# El_W_rfel.net
KiCad netlist of a schematic drawn in EAGLE
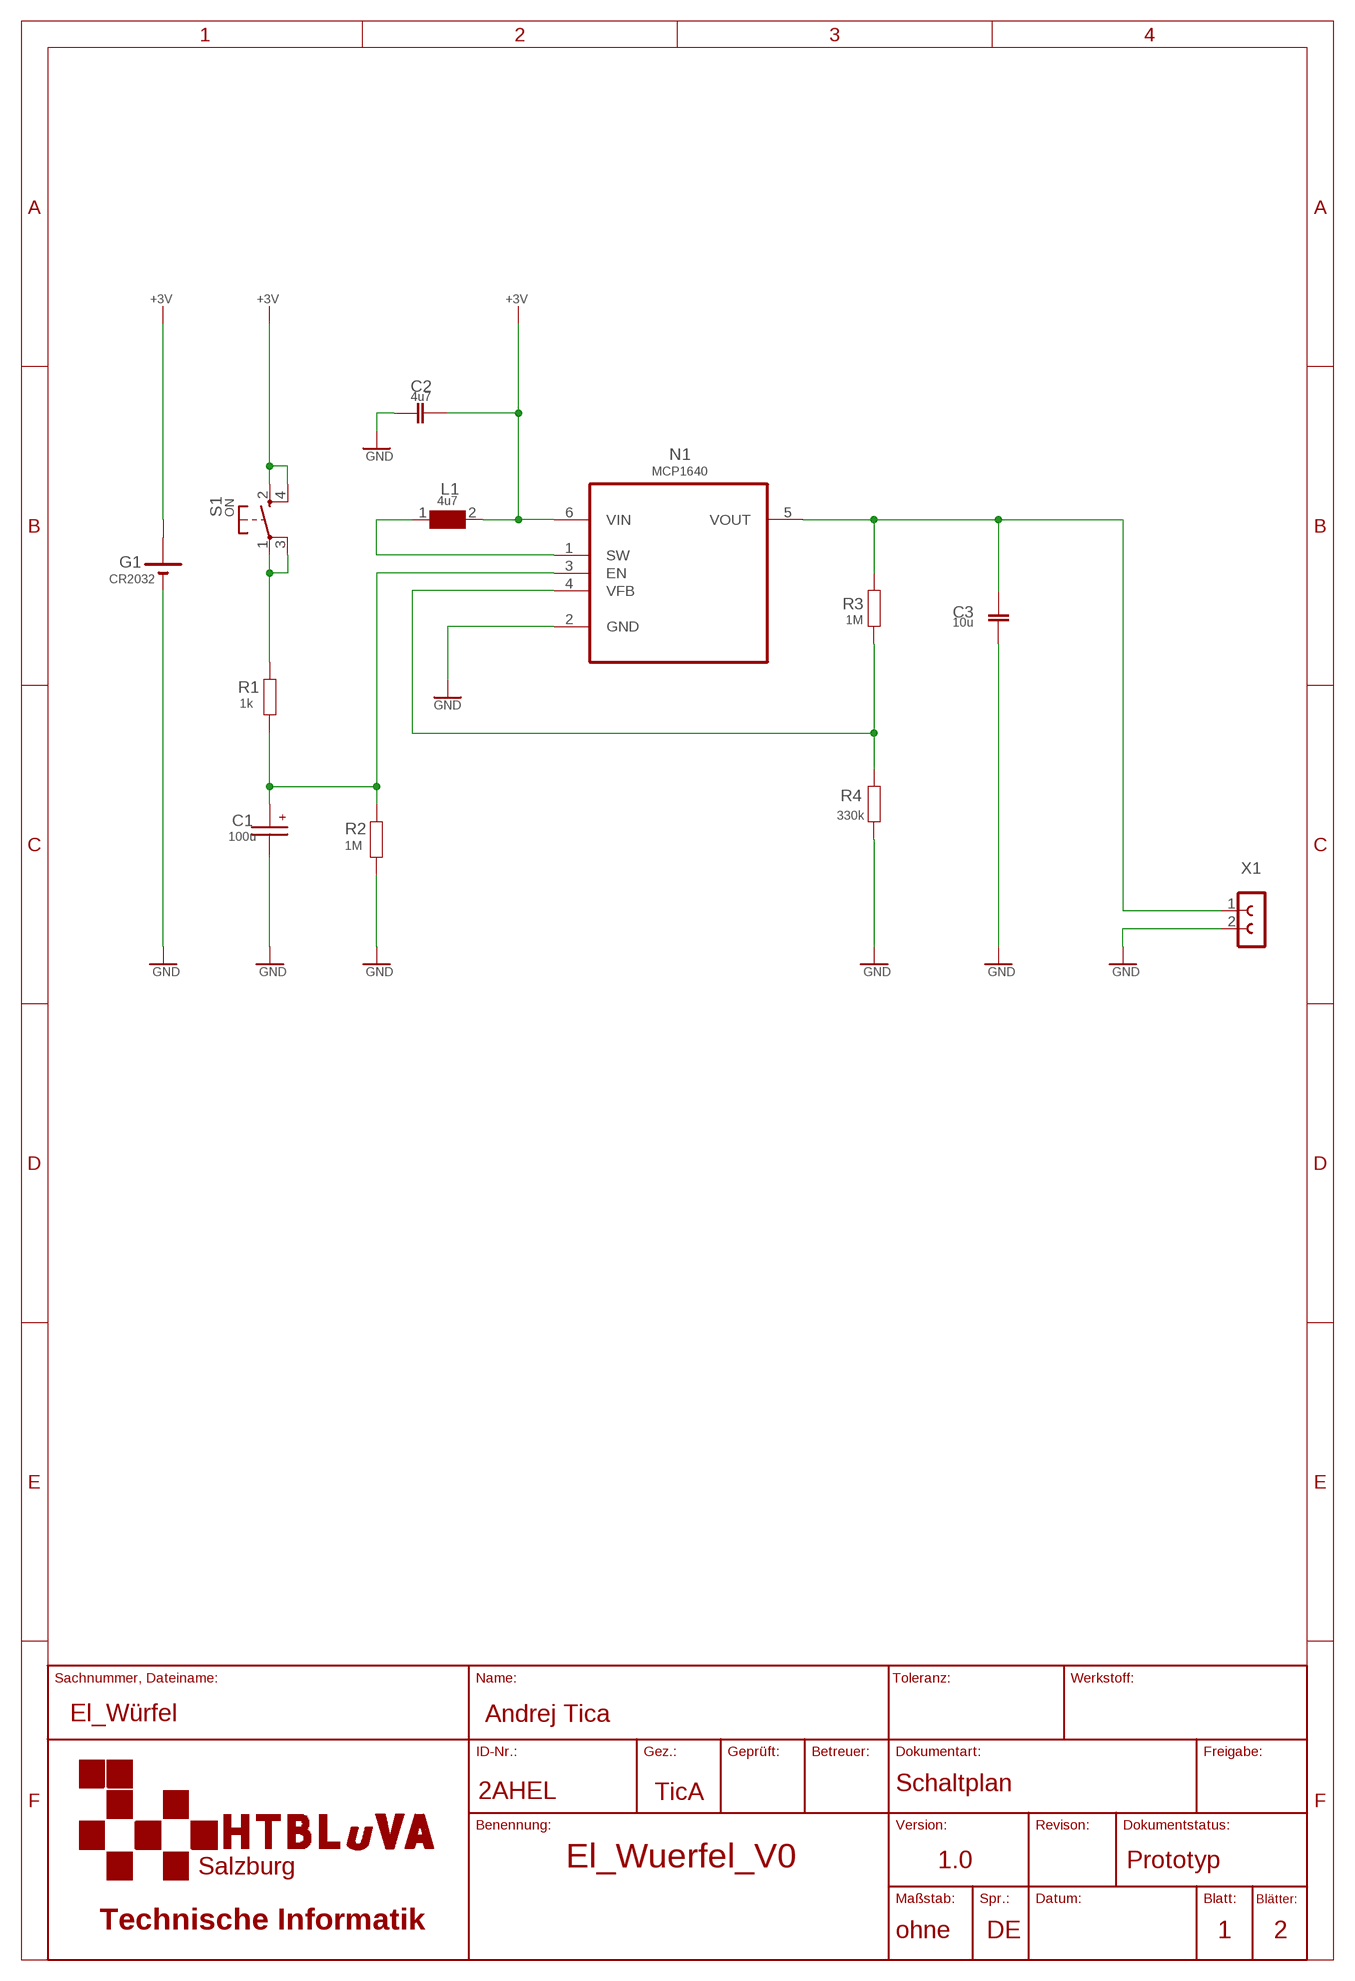
[diagram p0: schematic, sheet 1]
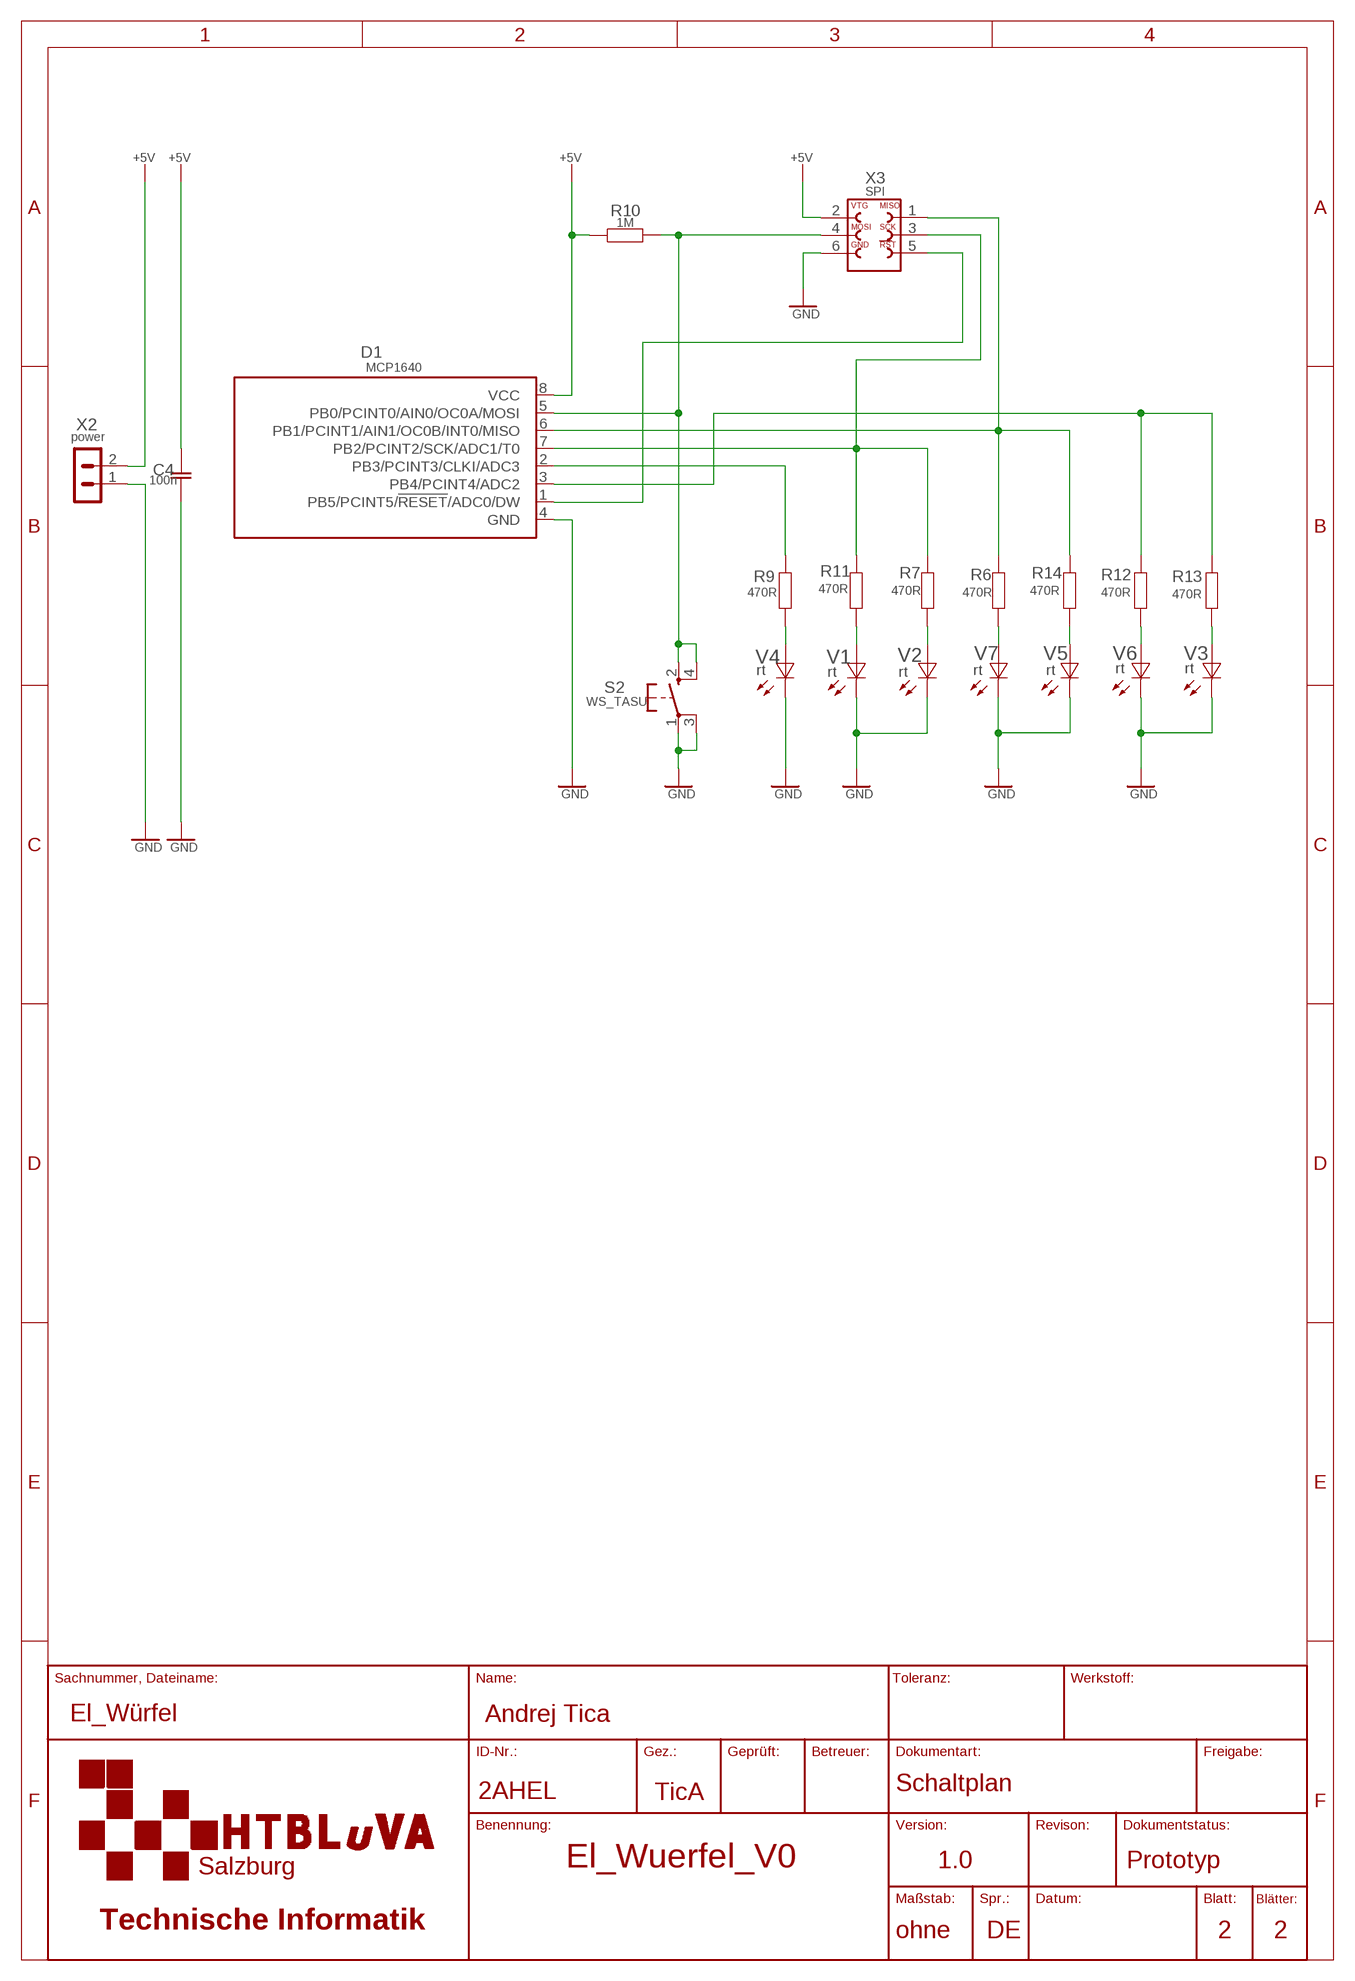
[diagram p1: schematic, sheet 2]

(export (version "E")
  (design (tool "Eeschema 10.0.6"))
  (components
    (comp (ref "C1")
      (value "100u")
      (footprint "eagle-import:B_3528-21R")
      (libsource (lib "eagle-import") (part "CPOL-V_B/3528-21R"))
    )
    (comp (ref "C2")
      (value "4u7")
      (footprint "eagle-import:MYLIB_C1206")
      (libsource (lib "eagle-import") (part "rcl_TicA_C-EU1206"))
    )
    (comp (ref "C3")
      (value "10u")
      (footprint "eagle-import:MYLIB_C1206")
      (libsource (lib "eagle-import") (part "rcl_TicA_C-EU1206"))
    )
    (comp (ref "G1")
      (value "CR2032")
      (footprint "eagle-import:MYLIB_CR2032")
      (libsource (lib "eagle-import") (part "KNOPFZELLE3V2CR"))
    )
    (comp (ref "L1")
      (value "4u7")
      (footprint "eagle-import:WE-PD2_4532")
      (libsource (lib "eagle-import") (part "WE-PD2_4532"))
    )
    (comp (ref "N1")
      (value "MCP1640")
      (footprint "eagle-import:SOT95P270X145-6N")
      (fields (field (name "MPN") "MCP1640BT-I/CHY"))
      (libsource (lib "eagle-import") (part "MCP1640BT-I/CHY"))
    )
    (comp (ref "R1")
      (value "1k")
      (footprint "eagle-import:MYRCL_R1206")
      (libsource (lib "eagle-import") (part "Netzteil_WenN2016_RCL_R-EU_R1206"))
    )
    (comp (ref "R2")
      (value "1M")
      (footprint "eagle-import:MYRCL_R1206")
      (libsource (lib "eagle-import") (part "Netzteil_WenN2016_RCL_R-EU_R1206"))
    )
    (comp (ref "R3")
      (value "1M")
      (footprint "eagle-import:MYRCL_R1206")
      (libsource (lib "eagle-import") (part "Netzteil_WenN2016_RCL_R-EU_R1206"))
    )
    (comp (ref "R4")
      (value "330k")
      (footprint "eagle-import:MYRCL_R1206")
      (libsource (lib "eagle-import") (part "Netzteil_WenN2016_RCL_R-EU_R1206"))
    )
    (comp (ref "S1")
      (value "ON")
      (footprint "eagle-import:WE_436331045822")
      (libsource (lib "eagle-import") (part "TASTE10-XXSMD_LW"))
    )
    (comp (ref "X1")
      (value "BU-LEISTE2")
      (footprint "eagle-import:1X02-SPF-WW")
      (libsource (lib "eagle-import") (part "BU-LEISTE2"))
    )
    (comp (ref "C4")
      (value "100n")
      (footprint "eagle-import:MYLIB_C1206")
      (libsource (lib "eagle-import") (part "C-EU1206"))
    )
    (comp (ref "D1")
      (value "MCP1640")
      (footprint "eagle-import:8S2_W")
      (libsource (lib "eagle-import") (part "TINY13SF"))
    )
    (comp (ref "R6")
      (value "470R")
      (footprint "eagle-import:MYRCL_M1206")
      (libsource (lib "eagle-import") (part "RCL_R-EU_M1206"))
    )
    (comp (ref "R7")
      (value "470R")
      (footprint "eagle-import:MYRCL_M1206")
      (libsource (lib "eagle-import") (part "RCL_R-EU_M1206"))
    )
    (comp (ref "R9")
      (value "470R")
      (footprint "eagle-import:MYRCL_M1206")
      (libsource (lib "eagle-import") (part "RCL_R-EU_M1206"))
    )
    (comp (ref "R10")
      (value "1M")
      (footprint "eagle-import:MYRCL_M1206")
      (libsource (lib "eagle-import") (part "RCL_R-EU_M1206"))
    )
    (comp (ref "R11")
      (value "470R")
      (footprint "eagle-import:MYRCL_M1206")
      (libsource (lib "eagle-import") (part "RCL_R-EU_M1206"))
    )
    (comp (ref "R12")
      (value "470R")
      (footprint "eagle-import:MYRCL_M1206")
      (libsource (lib "eagle-import") (part "RCL_R-EU_M1206"))
    )
    (comp (ref "R13")
      (value "470R")
      (footprint "eagle-import:MYRCL_M1206")
      (libsource (lib "eagle-import") (part "RCL_R-EU_M1206"))
    )
    (comp (ref "R14")
      (value "470R")
      (footprint "eagle-import:MYRCL_M1206")
      (libsource (lib "eagle-import") (part "RCL_R-EU_M1206"))
    )
    (comp (ref "S2")
      (value "WS_TASU")
      (footprint "eagle-import:WE_436331045822")
      (libsource (lib "eagle-import") (part "TASTE10-XXWE"))
    )
    (comp (ref "V1")
      (value "rt")
      (footprint "eagle-import:MYDIODE_CHIPLED_1206")
      (libsource (lib "eagle-import") (part "DIODE_LEDCHIPLED_1206"))
    )
    (comp (ref "V2")
      (value "rt")
      (footprint "eagle-import:MYDIODE_CHIPLED_1206")
      (libsource (lib "eagle-import") (part "DIODE_LEDCHIPLED_1206"))
    )
    (comp (ref "V3")
      (value "rt")
      (footprint "eagle-import:MYDIODE_CHIPLED_1206")
      (libsource (lib "eagle-import") (part "DIODE_LEDCHIPLED_1206"))
    )
    (comp (ref "V4")
      (value "rt")
      (footprint "eagle-import:MYDIODE_CHIPLED_1206")
      (libsource (lib "eagle-import") (part "DIODE_LEDCHIPLED_1206"))
    )
    (comp (ref "V5")
      (value "rt")
      (footprint "eagle-import:MYDIODE_CHIPLED_1206")
      (libsource (lib "eagle-import") (part "DIODE_LEDCHIPLED_1206"))
    )
    (comp (ref "V6")
      (value "rt")
      (footprint "eagle-import:MYDIODE_CHIPLED_1206")
      (libsource (lib "eagle-import") (part "DIODE_LEDCHIPLED_1206"))
    )
    (comp (ref "V7")
      (value "rt")
      (footprint "eagle-import:MYDIODE_CHIPLED_1206")
      (libsource (lib "eagle-import") (part "DIODE_LEDCHIPLED_1206"))
    )
    (comp (ref "X2")
      (value "power")
      (footprint "eagle-import:02P")
      (libsource (lib "eagle-import") (part "M02"))
    )
    (comp (ref "X3")
      (value "SPI")
      (footprint "eagle-import:690367280676_NEU")
      (libsource (lib "eagle-import") (part "610006243021SMT_WR_MM_NEU"))
    )
  )
  (nets
    (net (code "1") (name "+3V") (class "Default")
      (node (ref "C2") (pin "-") (pinfunction "1_-") (pintype "passive"))
      (node (ref "G1") (pin "+@1") (pinfunction "+_+@1") (pintype "passive"))
      (node (ref "L1") (pin "2") (pinfunction "2_2") (pintype "passive"))
      (node (ref "N1") (pin "6") (pinfunction "VIN_6") (pintype "input"))
      (node (ref "S1") (pin "2") (pinfunction "S_2") (pintype "passive"))
      (node (ref "S1") (pin "4") (pinfunction "S1_4") (pintype "passive"))
    )
    (net (code "2") (name "+5V") (class "Default")
      (node (ref "C4") (pin "-") (pinfunction "1_-") (pintype "passive"))
      (node (ref "D1") (pin "8") (pinfunction "VCC_8") (pintype "power_in"))
      (node (ref "R10") (pin "1") (pinfunction "1_1") (pintype "passive"))
      (node (ref "X2") (pin "2") (pinfunction "2_2") (pintype "passive"))
      (node (ref "X3") (pin "2") (pinfunction "2_2") (pintype "passive"))
    )
    (net (code "3") (name "GND") (class "Default")
      (node (ref "C1") (pin "-") (pinfunction "-_-") (pintype "passive"))
      (node (ref "C2") (pin "+") (pinfunction "2_+") (pintype "passive"))
      (node (ref "C3") (pin "+") (pinfunction "2_+") (pintype "passive"))
      (node (ref "C4") (pin "+") (pinfunction "2_+") (pintype "passive"))
      (node (ref "D1") (pin "4") (pinfunction "GND_4") (pintype "power_in"))
      (node (ref "G1") (pin "-") (pinfunction "-_-") (pintype "passive"))
      (node (ref "N1") (pin "2") (pinfunction "GND_2") (pintype "passive"))
      (node (ref "R2") (pin "1") (pinfunction "1_1") (pintype "passive"))
      (node (ref "R4") (pin "1") (pinfunction "1_1") (pintype "passive"))
      (node (ref "S2") (pin "1") (pinfunction "P_1") (pintype "passive"))
      (node (ref "S2") (pin "3") (pinfunction "P1_3") (pintype "passive"))
      (node (ref "V1") (pin "C") (pinfunction "C_C") (pintype "passive"))
      (node (ref "V2") (pin "C") (pinfunction "C_C") (pintype "passive"))
      (node (ref "V3") (pin "C") (pinfunction "C_C") (pintype "passive"))
      (node (ref "V4") (pin "C") (pinfunction "C_C") (pintype "passive"))
      (node (ref "V5") (pin "C") (pinfunction "C_C") (pintype "passive"))
      (node (ref "V6") (pin "C") (pinfunction "C_C") (pintype "passive"))
      (node (ref "V7") (pin "C") (pinfunction "C_C") (pintype "passive"))
      (node (ref "X1") (pin "2") (pinfunction "2_2") (pintype "passive"))
      (node (ref "X2") (pin "1") (pinfunction "1_1") (pintype "passive"))
      (node (ref "X3") (pin "6") (pinfunction "6_6") (pintype "passive"))
    )
    (net (code "4") (name "Net-(C3-1)") (class "Default")
      (node (ref "C3") (pin "-") (pinfunction "1_-") (pintype "passive"))
      (node (ref "N1") (pin "5") (pinfunction "VOUT_5") (pintype "output"))
      (node (ref "R3") (pin "2") (pinfunction "2_2") (pintype "passive"))
      (node (ref "X1") (pin "1") (pinfunction "1_1") (pintype "passive"))
    )
    (net (code "5") (name "Net-(D1-PB0{slash}PCINT0{slash}AIN0{slash}OC0A{slash}MOSI)") (class "Default")
      (node (ref "D1") (pin "5") (pinfunction "PB0/PCINT0/AIN0/OC0A/MOSI_5") (pintype "bidirectional"))
      (node (ref "R10") (pin "2") (pinfunction "2_2") (pintype "passive"))
      (node (ref "S2") (pin "2") (pinfunction "S_2") (pintype "passive"))
      (node (ref "S2") (pin "4") (pinfunction "S1_4") (pintype "passive"))
      (node (ref "X3") (pin "4") (pinfunction "4_4") (pintype "passive"))
    )
    (net (code "6") (name "Net-(D1-PB1{slash}PCINT1{slash}AIN1{slash}OC0B{slash}INT0{slash}MISO)") (class "Default")
      (node (ref "D1") (pin "6") (pinfunction "PB1/PCINT1/AIN1/OC0B/INT0/MISO_6") (pintype "bidirectional"))
      (node (ref "R14") (pin "2") (pinfunction "2_2") (pintype "passive"))
      (node (ref "R6") (pin "2") (pinfunction "2_2") (pintype "passive"))
      (node (ref "X3") (pin "1") (pinfunction "1_1") (pintype "passive"))
    )
    (net (code "7") (name "Net-(D1-PB2{slash}PCINT2{slash}SCK{slash}ADC1{slash}T0)") (class "Default")
      (node (ref "D1") (pin "7") (pinfunction "PB2/PCINT2/SCK/ADC1/T0_7") (pintype "bidirectional"))
      (node (ref "R11") (pin "2") (pinfunction "2_2") (pintype "passive"))
      (node (ref "R7") (pin "2") (pinfunction "2_2") (pintype "passive"))
      (node (ref "X3") (pin "3") (pinfunction "3_3") (pintype "passive"))
    )
    (net (code "8") (name "Net-(D1-PB3{slash}PCINT3{slash}CLKI{slash}ADC3)") (class "Default")
      (node (ref "D1") (pin "2") (pinfunction "PB3/PCINT3/CLKI/ADC3_2") (pintype "bidirectional"))
      (node (ref "R9") (pin "2") (pinfunction "2_2") (pintype "passive"))
    )
    (net (code "9") (name "Net-(D1-PB4{slash}PCINT4{slash}ADC2)") (class "Default")
      (node (ref "D1") (pin "3") (pinfunction "PB4/PCINT4/ADC2_3") (pintype "bidirectional"))
      (node (ref "R12") (pin "2") (pinfunction "2_2") (pintype "passive"))
      (node (ref "R13") (pin "2") (pinfunction "2_2") (pintype "passive"))
    )
    (net (code "10") (name "Net-(D1-PB5{slash}PCINT5{slash}~{RESET}{slash}ADC0{slash}DW)") (class "Default")
      (node (ref "D1") (pin "1") (pinfunction "PB5/PCINT5/~{RESET}/ADC0/DW_1") (pintype "bidirectional"))
      (node (ref "X3") (pin "5") (pinfunction "5_5") (pintype "passive"))
    )
    (net (code "11") (name "Net-(N1-EN)") (class "Default")
      (node (ref "C1") (pin "+") (pinfunction "+_+") (pintype "passive"))
      (node (ref "N1") (pin "3") (pinfunction "EN_3") (pintype "input"))
      (node (ref "R1") (pin "1") (pinfunction "1_1") (pintype "passive"))
      (node (ref "R2") (pin "2") (pinfunction "2_2") (pintype "passive"))
    )
    (net (code "12") (name "Net-(N1-SW)") (class "Default")
      (node (ref "L1") (pin "1") (pinfunction "1_1") (pintype "passive"))
      (node (ref "N1") (pin "1") (pinfunction "SW_1") (pintype "input"))
    )
    (net (code "13") (name "Net-(N1-VFB)") (class "Default")
      (node (ref "N1") (pin "4") (pinfunction "VFB_4") (pintype "input"))
      (node (ref "R3") (pin "1") (pinfunction "1_1") (pintype "passive"))
      (node (ref "R4") (pin "2") (pinfunction "2_2") (pintype "passive"))
    )
    (net (code "14") (name "Net-(R6-Pad1)") (class "Default")
      (node (ref "R6") (pin "1") (pinfunction "1_1") (pintype "passive"))
      (node (ref "V7") (pin "A") (pinfunction "A_A") (pintype "passive"))
    )
    (net (code "15") (name "Net-(R7-Pad1)") (class "Default")
      (node (ref "R7") (pin "1") (pinfunction "1_1") (pintype "passive"))
      (node (ref "V2") (pin "A") (pinfunction "A_A") (pintype "passive"))
    )
    (net (code "16") (name "Net-(R9-Pad1)") (class "Default")
      (node (ref "R9") (pin "1") (pinfunction "1_1") (pintype "passive"))
      (node (ref "V4") (pin "A") (pinfunction "A_A") (pintype "passive"))
    )
    (net (code "17") (name "Net-(R11-Pad1)") (class "Default")
      (node (ref "R11") (pin "1") (pinfunction "1_1") (pintype "passive"))
      (node (ref "V1") (pin "A") (pinfunction "A_A") (pintype "passive"))
    )
    (net (code "18") (name "Net-(R12-Pad1)") (class "Default")
      (node (ref "R12") (pin "1") (pinfunction "1_1") (pintype "passive"))
      (node (ref "V6") (pin "A") (pinfunction "A_A") (pintype "passive"))
    )
    (net (code "19") (name "Net-(R13-Pad1)") (class "Default")
      (node (ref "R13") (pin "1") (pinfunction "1_1") (pintype "passive"))
      (node (ref "V3") (pin "A") (pinfunction "A_A") (pintype "passive"))
    )
    (net (code "20") (name "Net-(R14-Pad1)") (class "Default")
      (node (ref "R14") (pin "1") (pinfunction "1_1") (pintype "passive"))
      (node (ref "V5") (pin "A") (pinfunction "A_A") (pintype "passive"))
    )
    (net (code "21") (name "Net-(S1-P)") (class "Default")
      (node (ref "R1") (pin "2") (pinfunction "2_2") (pintype "passive"))
      (node (ref "S1") (pin "1") (pinfunction "P_1") (pintype "passive"))
      (node (ref "S1") (pin "3") (pinfunction "P1_3") (pintype "passive"))
    )
    (net (code "22") (name "unconnected-(G1-+-Pad+@2)") (class "Default")
      (node (ref "G1") (pin "+@2") (pinfunction "+_+@2") (pintype "passive"))
    )
  )
)
